# 4G_GATEWAY.net
KiCad netlist of a schematic drawn in Altium Designer
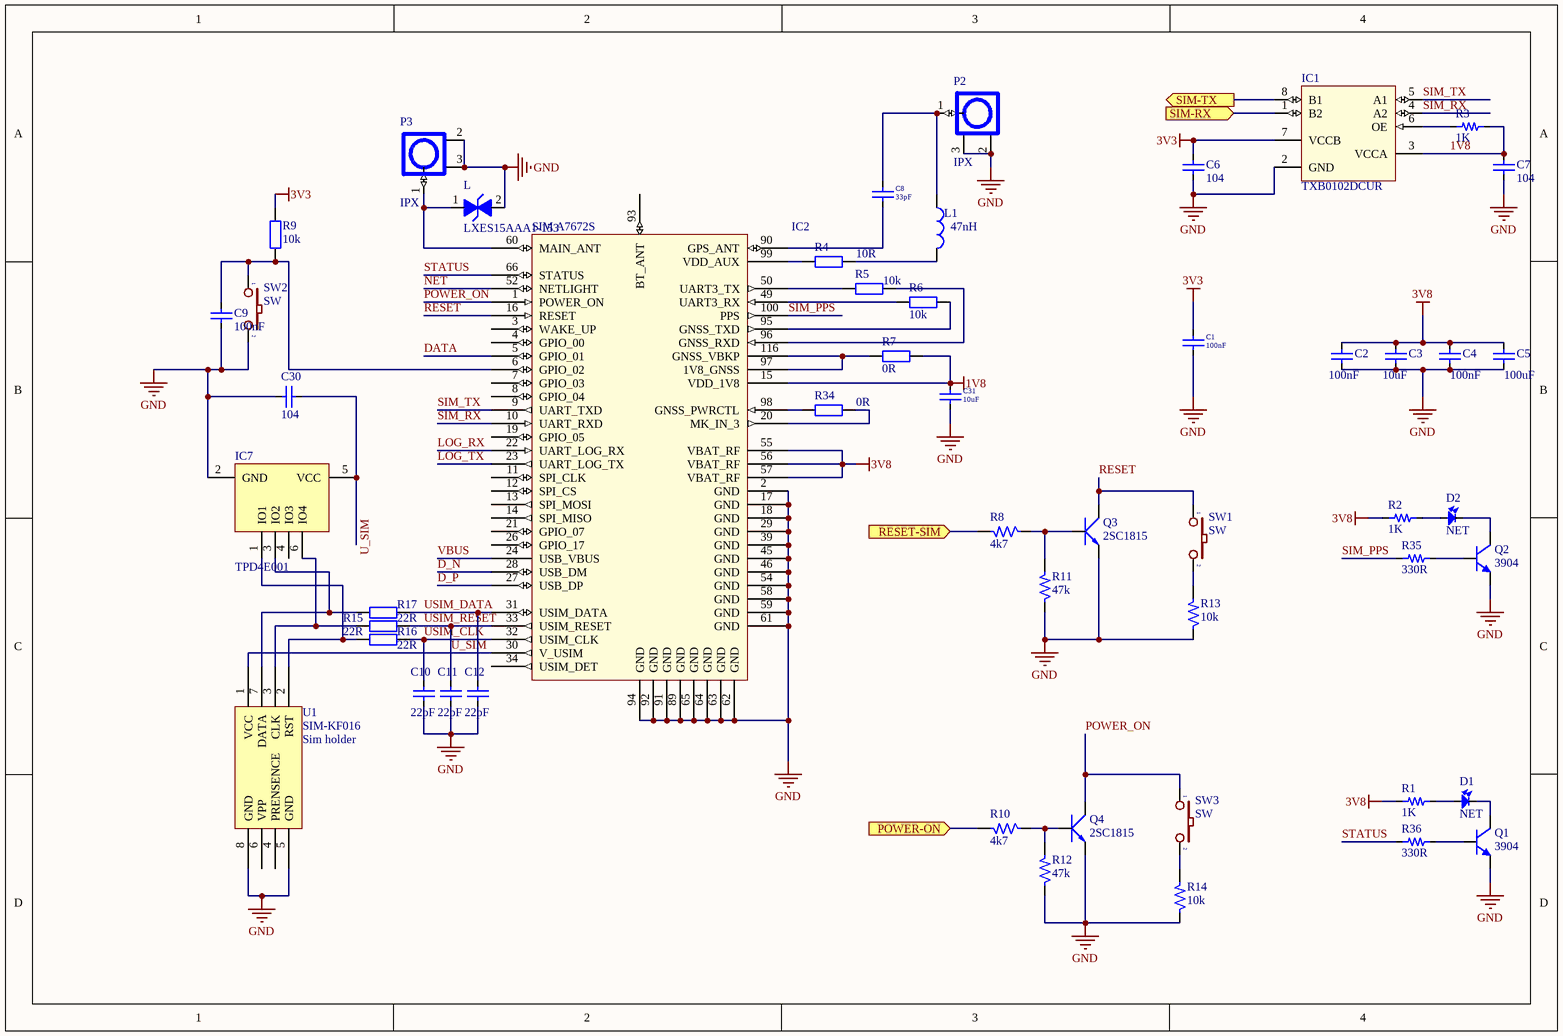
[diagram p0: 4G_GATEWAY.SchDoc]

(export (version "E")
  (design (tool "Eeschema 10.0.6"))
  (components
    (comp (ref "C1")
      (value "100nF")
      (footprint "CAP_0805")
      (description "Capacitor")
      (fields (field (name "PUBLISHER") "Altium Limited"))
      (libsource (lib "SIM_devkit") (part "CapSMD_5"))
    )
    (comp (ref "C2")
      (value "100nF")
      (footprint "CAP_0805")
      (description "Capacitor")
      (fields (field (name "PUBLISHER") "Altium Limited"))
      (libsource (lib "SIM_devkit") (part "CapSMD_9"))
    )
    (comp (ref "C3")
      (value "10uF")
      (footprint "CAP_0805")
      (description "Capacitor")
      (fields (field (name "PUBLISHER") "Altium Limited"))
      (libsource (lib "SIM_devkit") (part "CapSMD_9"))
    )
    (comp (ref "C4")
      (value "100nF")
      (footprint "CAP_0805")
      (description "Capacitor")
      (fields (field (name "PUBLISHER") "Altium Limited"))
      (libsource (lib "SIM_devkit") (part "CapSMD_9"))
    )
    (comp (ref "C5")
      (value "100uF")
      (footprint "CAP_0805")
      (description "Capacitor")
      (fields (field (name "PUBLISHER") "Altium Limited"))
      (libsource (lib "SIM_devkit") (part "CapSMD_9"))
    )
    (comp (ref "C6")
      (value "104")
      (footprint "CAP_0805")
      (description "Capacitor")
      (fields (field (name "PUBLISHER") "Altium Limited"))
      (libsource (lib "SIM_devkit") (part "CapSMD_9"))
    )
    (comp (ref "C7")
      (value "104")
      (footprint "CAP_0805")
      (description "Capacitor")
      (fields (field (name "PUBLISHER") "Altium Limited"))
      (libsource (lib "SIM_devkit") (part "CapSMD_9"))
    )
    (comp (ref "C8")
      (value "33pF")
      (footprint "CAP_0805")
      (description "Capacitor")
      (fields (field (name "PUBLISHER") "Altium Limited"))
      (libsource (lib "SIM_devkit") (part "CapSMD_1"))
    )
    (comp (ref "C9")
      (value "100nF")
      (footprint "CAP_0805")
      (description "Capacitor")
      (fields (field (name "PUBLISHER") "Altium Limited"))
      (libsource (lib "My Library") (part "CapSMD"))
    )
    (comp (ref "C10")
      (value "22pF")
      (footprint "CAP_0805")
      (description "Capacitor")
      (fields (field (name "PUBLISHER") "Altium Limited"))
      (libsource (lib "My Library") (part "CapSMD"))
    )
    (comp (ref "C11")
      (value "22pF")
      (footprint "CAP_0805")
      (description "Capacitor")
      (fields (field (name "PUBLISHER") "Altium Limited"))
      (libsource (lib "My Library") (part "CapSMD"))
    )
    (comp (ref "C12")
      (value "22pF")
      (footprint "CAP_0805")
      (description "Capacitor")
      (fields (field (name "PUBLISHER") "Altium Limited"))
      (libsource (lib "My Library") (part "CapSMD"))
    )
    (comp (ref "C30")
      (value "104")
      (footprint "CAP_0805")
      (description "Capacitor")
      (fields (field (name "PUBLISHER") "Altium Limited"))
      (libsource (lib "My Library") (part "CapSMD"))
    )
    (comp (ref "C31")
      (value "10uF")
      (footprint "CAP_0805")
      (description "Capacitor")
      (fields (field (name "PUBLISHER") "Altium Limited"))
      (libsource (lib "SIM_devkit") (part "CapSMD_1"))
    )
    (comp (ref "D1")
      (value "NET")
      (footprint "LED-0805-Blue")
      (description "LED Single colour Green and Red")
      (libsource (lib "SIM_devkit") (part "LED_2"))
    )
    (comp (ref "D2")
      (value "NET")
      (footprint "LED-0805-Blue")
      (description "LED Single colour Green and Red")
      (libsource (lib "SIM_devkit") (part "LED_2"))
    )
    (comp (ref "IC1")
      (value "TXB0102DCUR")
      (footprint "SOP50P310X90-8N")
      (description "IC TRNSLTR BIDIRECTIONAL US8")
      (fields (field (name "MANUFACTURER") "Texas Instruments"))
      (libsource (lib "SIM_devkit") (part "TXB0102DCUR"))
    )
    (comp (ref "IC2")
      (value "SIM A7672S")
      (footprint "A7672S")
      (description "SIM A7672S-CAT-M1")
      (libsource (lib "My Library") (part "SIM A7672S"))
    )
    (comp (ref "IC7")
      (value "TPD4E001")
      (footprint "SOT23-6")
      (fields (field (name "MANUFACTURER") "Texas Instruments") (field (name "PART NUMBER") "TPD4E001RDBVR"))
      (libsource (lib "SIM_devkit") (part "TPD4E001_1"))
    )
    (comp (ref "L")
      (value "LXES15AAA1-153")
      (footprint "INDC1005X45")
      (description "Clamp Ipp Tvs Diode Surface Mount 1005")
      (fields (field (name "MF") "Murata") (field (name "DIGI-KEY_PART_NUMBER") "490-13210-1-ND"))
      (libsource (lib "LXES15AAA1-153") (part "LXES15AAA1-153"))
    )
    (comp (ref "L1")
      (value "47nH")
      (footprint "L-0805")
      (description "22µH Shielded Inductor 1.65A 96mOhm Max Nonstandard")
      (fields (field (name "MANUFACTURER") "Bourns Inc.") (field (name "PART NUMBER") "SRR0745A-220M"))
      (libsource (lib "SIM_devkit") (part "L1"))
    )
    (comp (ref "P2")
      (value "IPX")
      (footprint "IPXS")
      (description "Antenna GSM GPS")
      (fields
        (field (name "MANUFACTURER") "TE Connectivity AMP Connectors")
        (field (name "PART NUMBER") "2334884-1")
      )
      (libsource (lib "SIM_devkit") (part "IPXSx66"))
    )
    (comp (ref "P3")
      (value "IPX")
      (footprint "IPXS")
      (description "Antenna GSM GPS")
      (fields
        (field (name "MANUFACTURER") "TE Connectivity AMP Connectors")
        (field (name "PART NUMBER") "2334884-1")
      )
      (libsource (lib "SIM_devkit") (part "IPXSx66"))
    )
    (comp (ref "Q1") (value "3904") (footprint "SOT23") (libsource (lib "SIM_devkit") (part "MMBT3904")))
    (comp (ref "Q2") (value "3904") (footprint "SOT23") (libsource (lib "SIM_devkit") (part "MMBT3904")))
    (comp (ref "Q3")
      (value "2SC1815")
      (footprint "SOT23")
      (description "NPN 600mW, ECB")
      (libsource (lib "My Library 2") (part "2SC1815"))
    )
    (comp (ref "Q4")
      (value "2SC1815")
      (footprint "SOT23")
      (description "NPN 600mW, ECB")
      (libsource (lib "My Library 2") (part "2SC1815"))
    )
    (comp (ref "R1")
      (value "1K")
      (footprint "RES-SMD-0805")
      (description "Resistor")
      (fields
        (field (name "MANUFACTURER") "Generic Components")
        (field (name "PUBLISHER") "Altium Hobart Technology Centre")
      )
      (libsource (lib "SIM_devkit") (part "Resistor - SMD"))
    )
    (comp (ref "R2")
      (value "1K")
      (footprint "RES-SMD-0805")
      (description "Resistor")
      (fields
        (field (name "MANUFACTURER") "Generic Components")
        (field (name "PUBLISHER") "Altium Hobart Technology Centre")
      )
      (libsource (lib "SIM_devkit") (part "Resistor - SMD"))
    )
    (comp (ref "R3")
      (value "1K")
      (footprint "RES-SMD-0805")
      (description "Resistor")
      (fields
        (field (name "MANUFACTURER") "Generic Components")
        (field (name "PUBLISHER") "Altium Hobart Technology Centre")
      )
      (libsource (lib "SIM_devkit") (part "Resistor - SMD"))
    )
    (comp (ref "R4")
      (value "10R")
      (footprint "RES-SMD-0805")
      (description "Resistor SMD")
      (fields
        (field (name "MANUFACTURER") "Generic Components")
        (field (name "PUBLISHER") "Altium Hobart Technology Centre")
      )
      (libsource (lib "My Library") (part "Resistor - SMD"))
    )
    (comp (ref "R5")
      (value "10k")
      (footprint "RES-SMD-0805")
      (description "Resistor SMD")
      (fields
        (field (name "MANUFACTURER") "Generic Components")
        (field (name "PUBLISHER") "Altium Hobart Technology Centre")
      )
      (libsource (lib "My Library") (part "Resistor - SMD"))
    )
    (comp (ref "R6")
      (value "10k")
      (footprint "RES-SMD-0805")
      (description "Resistor SMD")
      (fields
        (field (name "MANUFACTURER") "Generic Components")
        (field (name "PUBLISHER") "Altium Hobart Technology Centre")
      )
      (libsource (lib "My Library") (part "Resistor - SMD"))
    )
    (comp (ref "R7")
      (value "0R")
      (footprint "RES-SMD-0805")
      (description "Resistor SMD")
      (fields
        (field (name "MANUFACTURER") "Generic Components")
        (field (name "PUBLISHER") "Altium Hobart Technology Centre")
      )
      (libsource (lib "My Library") (part "Resistor - SMD"))
    )
    (comp (ref "R8")
      (value "4k7")
      (footprint "RES-SMD-0805")
      (description "Resistor 1/4W")
      (libsource (lib "My Library 2") (part "R"))
    )
    (comp (ref "R9")
      (value "10k")
      (footprint "RES-SMD-0805")
      (description "Resistor SMD")
      (fields
        (field (name "MANUFACTURER") "Generic Components")
        (field (name "PUBLISHER") "Altium Hobart Technology Centre")
      )
      (libsource (lib "My Library") (part "Resistor - SMD"))
    )
    (comp (ref "R10")
      (value "4k7")
      (footprint "RES-SMD-0805")
      (description "Resistor 1/4W")
      (libsource (lib "My Library 2") (part "R"))
    )
    (comp (ref "R11")
      (value "47k")
      (footprint "RES-SMD-0805")
      (description "Resistor 1/4W")
      (libsource (lib "My Library 2") (part "R"))
    )
    (comp (ref "R12")
      (value "47k")
      (footprint "RES-SMD-0805")
      (description "Resistor 1/4W")
      (libsource (lib "My Library 2") (part "R"))
    )
    (comp (ref "R13")
      (value "10k")
      (footprint "RES-SMD-0805")
      (description "Resistor 1/4W")
      (libsource (lib "My Library 2") (part "R"))
    )
    (comp (ref "R14")
      (value "10k")
      (footprint "RES-SMD-0805")
      (description "Resistor 1/4W")
      (libsource (lib "My Library 2") (part "R"))
    )
    (comp (ref "R15")
      (value "22R")
      (footprint "RES-SMD-0805")
      (description "Resistor SMD")
      (fields
        (field (name "MANUFACTURER") "Generic Components")
        (field (name "PUBLISHER") "Altium Hobart Technology Centre")
      )
      (libsource (lib "My Library") (part "Resistor - SMD"))
    )
    (comp (ref "R16")
      (value "22R")
      (footprint "RES-SMD-0805")
      (description "Resistor SMD")
      (fields
        (field (name "MANUFACTURER") "Generic Components")
        (field (name "PUBLISHER") "Altium Hobart Technology Centre")
      )
      (libsource (lib "My Library") (part "Resistor - SMD"))
    )
    (comp (ref "R17")
      (value "22R")
      (footprint "RES-SMD-0805")
      (description "Resistor SMD")
      (fields
        (field (name "MANUFACTURER") "Generic Components")
        (field (name "PUBLISHER") "Altium Hobart Technology Centre")
      )
      (libsource (lib "My Library") (part "Resistor - SMD"))
    )
    (comp (ref "R34")
      (value "0R")
      (footprint "RES-SMD-0805")
      (description "Resistor SMD")
      (fields
        (field (name "MANUFACTURER") "Generic Components")
        (field (name "PUBLISHER") "Altium Hobart Technology Centre")
      )
      (libsource (lib "My Library") (part "Resistor - SMD"))
    )
    (comp (ref "R35")
      (value "330R")
      (footprint "RES-SMD-0805")
      (description "Resistor")
      (fields
        (field (name "MANUFACTURER") "Generic Components")
        (field (name "PUBLISHER") "Altium Hobart Technology Centre")
      )
      (libsource (lib "SIM_devkit") (part "Resistor - SMD"))
    )
    (comp (ref "R36")
      (value "330R")
      (footprint "RES-SMD-0805")
      (description "Resistor")
      (fields
        (field (name "MANUFACTURER") "Generic Components")
        (field (name "PUBLISHER") "Altium Hobart Technology Centre")
      )
      (libsource (lib "SIM_devkit") (part "Resistor - SMD"))
    )
    (comp (ref "SW1")
      (value "SW")
      (footprint "SW-SMD")
      (description "Switch button 2 pin")
      (libsource (lib "My Library 2") (part "SW2"))
    )
    (comp (ref "SW2")
      (value "SW")
      (footprint "SW-SMD")
      (description "Switch button 2 pin")
      (libsource (lib "My Library") (part "SW2"))
    )
    (comp (ref "SW3")
      (value "SW")
      (footprint "SW-SMD")
      (description "Switch button 2 pin")
      (libsource (lib "My Library 2") (part "SW2"))
    )
    (comp (ref "U1")
      (value "SIM-KF016")
      (footprint "SIM_MicroSIM 6P Flip")
      (description "SIM Card Holder KF-016")
      (fields (field (name "ALTIUM_VALUE") "Sim holder"))
      (libsource (lib "My Library") (part "Sim holder"))
    )
  )
  (nets
    (net (code "1") (name "/DATA") (class "Default")
      (node (ref "IC2") (pin "5") (pinfunction "GPIO_01_5") (pintype "bidirectional"))
    )
    (net (code "2") (name "/D_N") (class "Default")
      (node (ref "IC2") (pin "28") (pinfunction "USB_DM_28") (pintype "bidirectional"))
    )
    (net (code "3") (name "/D_P") (class "Default")
      (node (ref "IC2") (pin "27") (pinfunction "USB_DP_27") (pintype "bidirectional"))
    )
    (net (code "4") (name "/LOG_RX") (class "Default")
      (node (ref "IC2") (pin "22") (pinfunction "UART_LOG_RX_22") (pintype "input"))
    )
    (net (code "5") (name "/LOG_TX") (class "Default")
      (node (ref "IC2") (pin "23") (pinfunction "UART_LOG_TX_23") (pintype "output"))
    )
    (net (code "6") (name "/NET") (class "Default")
      (node (ref "IC2") (pin "52") (pinfunction "NETLIGHT_52") (pintype "bidirectional"))
    )
    (net (code "7") (name "/POWER-ON") (class "Default")
      (node (ref "R10") (pin "2") (pinfunction "2_2") (pintype "passive"))
    )
    (net (code "8") (name "/POWER_ON") (class "Default")
      (node (ref "IC2") (pin "1") (pinfunction "POWER_ON_1") (pintype "input"))
      (node (ref "Q4") (pin "2") (pinfunction "C_2") (pintype "passive"))
      (node (ref "SW3") (pin "1") (pinfunction "1_1") (pintype "passive"))
    )
    (net (code "9") (name "/RESET") (class "Default")
      (node (ref "IC2") (pin "16") (pinfunction "RESET_16") (pintype "input"))
      (node (ref "Q3") (pin "2") (pinfunction "C_2") (pintype "passive"))
      (node (ref "SW1") (pin "1") (pinfunction "1_1") (pintype "passive"))
    )
    (net (code "10") (name "/RESET-SIM") (class "Default")
      (node (ref "R8") (pin "2") (pinfunction "2_2") (pintype "passive"))
    )
    (net (code "11") (name "/SIM-RX") (class "Default")
      (node (ref "IC1") (pin "1") (pinfunction "B2_1") (pintype "bidirectional"))
    )
    (net (code "12") (name "/SIM-TX") (class "Default")
      (node (ref "IC1") (pin "8") (pinfunction "B1_8") (pintype "bidirectional"))
    )
    (net (code "13") (name "/SIM_PPS") (class "Default")
      (node (ref "IC2") (pin "100") (pinfunction "PPS_100") (pintype "output"))
      (node (ref "R35") (pin "1") (pinfunction "1_1") (pintype "passive"))
    )
    (net (code "14") (name "/SIM_RX") (class "Default")
      (node (ref "IC1") (pin "4") (pinfunction "A2_4") (pintype "bidirectional"))
      (node (ref "IC2") (pin "10") (pinfunction "UART_RXD_10") (pintype "input"))
    )
    (net (code "15") (name "/SIM_TX") (class "Default")
      (node (ref "IC1") (pin "5") (pinfunction "A1_5") (pintype "bidirectional"))
      (node (ref "IC2") (pin "9") (pinfunction "UART_TXD_9") (pintype "output"))
    )
    (net (code "16") (name "/STATUS") (class "Default")
      (node (ref "IC2") (pin "66") (pinfunction "STATUS_66") (pintype "bidirectional"))
      (node (ref "R36") (pin "1") (pinfunction "1_1") (pintype "passive"))
    )
    (net (code "17") (name "/USIM_CLK") (class "Default")
      (node (ref "C10") (pin "1") (pinfunction "1_1") (pintype "passive"))
      (node (ref "IC2") (pin "32") (pinfunction "USIM_CLK_32") (pintype "output"))
      (node (ref "R16") (pin "1") (pinfunction "1_1") (pintype "passive"))
    )
    (net (code "18") (name "/USIM_DATA") (class "Default")
      (node (ref "C12") (pin "1") (pinfunction "1_1") (pintype "passive"))
      (node (ref "IC2") (pin "31") (pinfunction "USIM_DATA_31") (pintype "bidirectional"))
      (node (ref "R17") (pin "1") (pinfunction "1_1") (pintype "passive"))
    )
    (net (code "19") (name "/USIM_RESET") (class "Default")
      (node (ref "C11") (pin "1") (pinfunction "1_1") (pintype "passive"))
      (node (ref "C30") (pin "1") (pinfunction "1_1") (pintype "passive"))
      (node (ref "IC2") (pin "30") (pinfunction "V_USIM_30") (pintype "output"))
      (node (ref "IC2") (pin "33") (pinfunction "USIM_RESET_33") (pintype "output"))
      (node (ref "IC7") (pin "5") (pinfunction "VCC_5") (pintype "passive"))
      (node (ref "R15") (pin "2") (pinfunction "2_2") (pintype "passive"))
      (node (ref "U1") (pin "1") (pinfunction "VCC_1") (pintype "passive"))
    )
    (net (code "20") (name "/VBUS") (class "Default")
      (node (ref "IC2") (pin "24") (pinfunction "USB_VBUS_24") (pintype "passive"))
    )
    (net (code "21") (name "1V8") (class "Default")
      (node (ref "C31") (pin "2") (pinfunction "2_2") (pintype "passive"))
      (node (ref "C7") (pin "2") (pinfunction "2_2") (pintype "passive"))
      (node (ref "IC1") (pin "3") (pinfunction "VCCA_3") (pintype "power_in"))
      (node (ref "IC2") (pin "15") (pinfunction "VDD_1V8_15") (pintype "passive"))
      (node (ref "R3") (pin "2") (pinfunction "2_2") (pintype "passive"))
      (node (ref "R7") (pin "1") (pinfunction "1_1") (pintype "passive"))
    )
    (net (code "22") (name "3V3") (class "Default")
      (node (ref "C1") (pin "2") (pinfunction "2_2") (pintype "passive"))
      (node (ref "C6") (pin "2") (pinfunction "2_2") (pintype "passive"))
      (node (ref "IC1") (pin "7") (pinfunction "VCCB_7") (pintype "power_in"))
      (node (ref "R9") (pin "2") (pinfunction "2_2") (pintype "passive"))
    )
    (net (code "23") (name "3V8") (class "Default")
      (node (ref "C2") (pin "2") (pinfunction "2_2") (pintype "passive"))
      (node (ref "C3") (pin "2") (pinfunction "2_2") (pintype "passive"))
      (node (ref "C4") (pin "2") (pinfunction "2_2") (pintype "passive"))
      (node (ref "C5") (pin "2") (pinfunction "2_2") (pintype "passive"))
      (node (ref "IC2") (pin "55") (pinfunction "VBAT_RF_55") (pintype "passive"))
      (node (ref "IC2") (pin "56") (pinfunction "VBAT_RF_56") (pintype "passive"))
      (node (ref "IC2") (pin "57") (pinfunction "VBAT_RF_57") (pintype "passive"))
      (node (ref "R1") (pin "1") (pinfunction "1_1") (pintype "passive"))
      (node (ref "R2") (pin "1") (pinfunction "1_1") (pintype "passive"))
    )
    (net (code "24") (name "GND") (class "Default")
      (node (ref "C1") (pin "1") (pinfunction "1_1") (pintype "passive"))
      (node (ref "C10") (pin "2") (pinfunction "2_2") (pintype "passive"))
      (node (ref "C11") (pin "2") (pinfunction "2_2") (pintype "passive"))
      (node (ref "C12") (pin "2") (pinfunction "2_2") (pintype "passive"))
      (node (ref "C2") (pin "1") (pinfunction "1_1") (pintype "passive"))
      (node (ref "C3") (pin "1") (pinfunction "1_1") (pintype "passive"))
      (node (ref "C30") (pin "2") (pinfunction "2_2") (pintype "passive"))
      (node (ref "C31") (pin "1") (pinfunction "1_1") (pintype "passive"))
      (node (ref "C4") (pin "1") (pinfunction "1_1") (pintype "passive"))
      (node (ref "C5") (pin "1") (pinfunction "1_1") (pintype "passive"))
      (node (ref "C6") (pin "1") (pinfunction "1_1") (pintype "passive"))
      (node (ref "C7") (pin "1") (pinfunction "1_1") (pintype "passive"))
      (node (ref "C9") (pin "1") (pinfunction "1_1") (pintype "passive"))
      (node (ref "IC1") (pin "2") (pinfunction "GND_2") (pintype "power_in"))
      (node (ref "IC2") (pin "17") (pinfunction "GND_17") (pintype "passive"))
      (node (ref "IC2") (pin "18") (pinfunction "GND_18") (pintype "passive"))
      (node (ref "IC2") (pin "2") (pinfunction "GND_2") (pintype "passive"))
      (node (ref "IC2") (pin "29") (pinfunction "GND_29") (pintype "passive"))
      (node (ref "IC2") (pin "39") (pinfunction "GND_39") (pintype "passive"))
      (node (ref "IC2") (pin "45") (pinfunction "GND_45") (pintype "passive"))
      (node (ref "IC2") (pin "46") (pinfunction "GND_46") (pintype "passive"))
      (node (ref "IC2") (pin "54") (pinfunction "GND_54") (pintype "passive"))
      (node (ref "IC2") (pin "58") (pinfunction "GND_58") (pintype "passive"))
      (node (ref "IC2") (pin "59") (pinfunction "GND_59") (pintype "passive"))
      (node (ref "IC2") (pin "61") (pinfunction "GND_61") (pintype "passive"))
      (node (ref "IC2") (pin "62") (pinfunction "GND_62") (pintype "passive"))
      (node (ref "IC2") (pin "63") (pinfunction "GND_63") (pintype "passive"))
      (node (ref "IC2") (pin "64") (pinfunction "GND_64") (pintype "passive"))
      (node (ref "IC2") (pin "65") (pinfunction "GND_65") (pintype "passive"))
      (node (ref "IC2") (pin "89") (pinfunction "GND_89") (pintype "passive"))
      (node (ref "IC2") (pin "91") (pinfunction "GND_91") (pintype "passive"))
      (node (ref "IC2") (pin "92") (pinfunction "GND_92") (pintype "passive"))
      (node (ref "IC2") (pin "94") (pinfunction "GND_94") (pintype "passive"))
      (node (ref "IC7") (pin "2") (pinfunction "GND_2") (pintype "passive"))
      (node (ref "L") (pin "2") (pinfunction "2_2") (pintype "passive"))
      (node (ref "P2") (pin "2") (pintype "passive"))
      (node (ref "P2") (pin "3") (pintype "passive"))
      (node (ref "P3") (pin "2") (pintype "passive"))
      (node (ref "P3") (pin "3") (pintype "passive"))
      (node (ref "Q1") (pin "2") (pinfunction "E_2") (pintype "passive"))
      (node (ref "Q2") (pin "2") (pinfunction "E_2") (pintype "passive"))
      (node (ref "Q3") (pin "1") (pinfunction "E_1") (pintype "passive"))
      (node (ref "Q4") (pin "1") (pinfunction "E_1") (pintype "passive"))
      (node (ref "R11") (pin "1") (pinfunction "1_1") (pintype "passive"))
      (node (ref "R12") (pin "1") (pinfunction "1_1") (pintype "passive"))
      (node (ref "R13") (pin "1") (pinfunction "1_1") (pintype "passive"))
      (node (ref "R14") (pin "1") (pinfunction "1_1") (pintype "passive"))
      (node (ref "SW2") (pin "2") (pinfunction "2_2") (pintype "passive"))
      (node (ref "U1") (pin "5") (pinfunction "GND_5") (pintype "passive"))
      (node (ref "U1") (pin "8") (pinfunction "GND_8") (pintype "passive"))
    )
    (net (code "25") (name "Net-(C8-Pad2)") (class "Default")
      (node (ref "C8") (pin "2") (pinfunction "2_2") (pintype "passive"))
      (node (ref "L1") (pin "1") (pinfunction "1_1") (pintype "passive"))
      (node (ref "P2") (pin "1") (pintype "bidirectional"))
    )
    (net (code "26") (name "Net-(D1-Pad1)") (class "Default")
      (node (ref "D1") (pin "1") (pinfunction "1_1") (pintype "passive"))
      (node (ref "R1") (pin "2") (pinfunction "2_2") (pintype "passive"))
    )
    (net (code "27") (name "Net-(D2-Pad1)") (class "Default")
      (node (ref "D2") (pin "1") (pinfunction "1_1") (pintype "passive"))
      (node (ref "R2") (pin "2") (pinfunction "2_2") (pintype "passive"))
    )
    (net (code "28") (name "Net-(IC1-OE)") (class "Default")
      (node (ref "IC1") (pin "6") (pinfunction "OE_6") (pintype "input"))
      (node (ref "R3") (pin "1") (pinfunction "1_1") (pintype "passive"))
    )
    (net (code "29") (name "Net-(IC2-1V8_GNSS)") (class "Default")
      (node (ref "IC2") (pin "116") (pinfunction "GNSS_VBKP_116") (pintype "passive"))
      (node (ref "IC2") (pin "97") (pinfunction "1V8_GNSS_97") (pintype "passive"))
      (node (ref "R7") (pin "2") (pinfunction "2_2") (pintype "passive"))
    )
    (net (code "30") (name "Net-(IC2-GNSS_PWRCTL)") (class "Default")
      (node (ref "IC2") (pin "98") (pinfunction "GNSS_PWRCTL_98") (pintype "input"))
      (node (ref "R34") (pin "2") (pinfunction "2_2") (pintype "passive"))
    )
    (net (code "31") (name "Net-(IC2-GNSS_RXD)") (class "Default")
      (node (ref "IC2") (pin "96") (pinfunction "GNSS_RXD_96") (pintype "input"))
      (node (ref "R5") (pin "1") (pinfunction "1_1") (pintype "passive"))
    )
    (net (code "32") (name "Net-(IC2-GNSS_TXD)") (class "Default")
      (node (ref "IC2") (pin "95") (pinfunction "GNSS_TXD_95") (pintype "output"))
      (node (ref "R6") (pin "1") (pinfunction "1_1") (pintype "passive"))
    )
    (net (code "33") (name "Net-(IC2-GPIO_02)") (class "Default")
      (node (ref "C9") (pin "2") (pinfunction "2_2") (pintype "passive"))
      (node (ref "IC2") (pin "6") (pinfunction "GPIO_02_6") (pintype "bidirectional"))
      (node (ref "R9") (pin "1") (pinfunction "1_1") (pintype "passive"))
      (node (ref "SW2") (pin "1") (pinfunction "1_1") (pintype "passive"))
    )
    (net (code "34") (name "Net-(IC2-GPS_ANT)") (class "Default")
      (node (ref "C8") (pin "1") (pinfunction "1_1") (pintype "passive"))
      (node (ref "IC2") (pin "90") (pinfunction "GPS_ANT_90") (pintype "bidirectional"))
    )
    (net (code "35") (name "Net-(IC2-MAIN_ANT)") (class "Default")
      (node (ref "IC2") (pin "60") (pinfunction "MAIN_ANT_60") (pintype "bidirectional"))
      (node (ref "L") (pin "1") (pinfunction "1_1") (pintype "passive"))
      (node (ref "P3") (pin "1") (pintype "bidirectional"))
    )
    (net (code "36") (name "Net-(IC2-MK_IN_3)") (class "Default")
      (node (ref "IC2") (pin "20") (pinfunction "MK_IN_3_20") (pintype "output"))
      (node (ref "R34") (pin "1") (pinfunction "1_1") (pintype "passive"))
    )
    (net (code "37") (name "Net-(IC2-UART3_RX)") (class "Default")
      (node (ref "IC2") (pin "49") (pinfunction "UART3_RX_49") (pintype "input"))
      (node (ref "R6") (pin "2") (pinfunction "2_2") (pintype "passive"))
    )
    (net (code "38") (name "Net-(IC2-UART3_TX)") (class "Default")
      (node (ref "IC2") (pin "50") (pinfunction "UART3_TX_50") (pintype "output"))
      (node (ref "R5") (pin "2") (pinfunction "2_2") (pintype "passive"))
    )
    (net (code "39") (name "Net-(IC2-VDD_AUX)") (class "Default")
      (node (ref "IC2") (pin "99") (pinfunction "VDD_AUX_99") (pintype "passive"))
      (node (ref "R4") (pin "2") (pinfunction "2_2") (pintype "passive"))
    )
    (net (code "40") (name "Net-(IC7-IO1)") (class "Default")
      (node (ref "IC7") (pin "1") (pinfunction "IO1_1") (pintype "passive"))
      (node (ref "R16") (pin "2") (pinfunction "2_2") (pintype "passive"))
      (node (ref "U1") (pin "2") (pinfunction "RST_2") (pintype "passive"))
    )
    (net (code "41") (name "Net-(IC7-IO2)") (class "Default")
      (node (ref "IC7") (pin "3") (pinfunction "IO2_3") (pintype "passive"))
      (node (ref "R17") (pin "2") (pinfunction "2_2") (pintype "passive"))
      (node (ref "U1") (pin "7") (pinfunction "DATA_7") (pintype "passive"))
    )
    (net (code "42") (name "Net-(IC7-IO4)") (class "Default")
      (node (ref "IC7") (pin "6") (pinfunction "IO4_6") (pintype "passive"))
      (node (ref "R15") (pin "1") (pinfunction "1_1") (pintype "passive"))
      (node (ref "U1") (pin "3") (pinfunction "CLK_3") (pintype "passive"))
    )
    (net (code "43") (name "Net-(L1-Pad2)") (class "Default")
      (node (ref "L1") (pin "2") (pinfunction "2_2") (pintype "passive"))
      (node (ref "R4") (pin "1") (pinfunction "1_1") (pintype "passive"))
    )
    (net (code "44") (name "Net-(Q1-B)") (class "Default")
      (node (ref "Q1") (pin "1") (pinfunction "B_1") (pintype "passive"))
      (node (ref "R36") (pin "2") (pinfunction "2_2") (pintype "passive"))
    )
    (net (code "45") (name "Net-(Q1-C)") (class "Default")
      (node (ref "D1") (pin "2") (pinfunction "2_2") (pintype "passive"))
      (node (ref "Q1") (pin "3") (pinfunction "C_3") (pintype "passive"))
    )
    (net (code "46") (name "Net-(Q2-B)") (class "Default")
      (node (ref "Q2") (pin "1") (pinfunction "B_1") (pintype "passive"))
      (node (ref "R35") (pin "2") (pinfunction "2_2") (pintype "passive"))
    )
    (net (code "47") (name "Net-(Q2-C)") (class "Default")
      (node (ref "D2") (pin "2") (pinfunction "2_2") (pintype "passive"))
      (node (ref "Q2") (pin "3") (pinfunction "C_3") (pintype "passive"))
    )
    (net (code "48") (name "Net-(Q3-B)") (class "Default")
      (node (ref "Q3") (pin "3") (pinfunction "B_3") (pintype "passive"))
      (node (ref "R11") (pin "2") (pinfunction "2_2") (pintype "passive"))
      (node (ref "R8") (pin "1") (pinfunction "1_1") (pintype "passive"))
    )
    (net (code "49") (name "Net-(Q4-B)") (class "Default")
      (node (ref "Q4") (pin "3") (pinfunction "B_3") (pintype "passive"))
      (node (ref "R10") (pin "1") (pinfunction "1_1") (pintype "passive"))
      (node (ref "R12") (pin "2") (pinfunction "2_2") (pintype "passive"))
    )
    (net (code "50") (name "Net-(R13-Pad2)") (class "Default")
      (node (ref "R13") (pin "2") (pinfunction "2_2") (pintype "passive"))
      (node (ref "SW1") (pin "2") (pinfunction "2_2") (pintype "passive"))
    )
    (net (code "51") (name "Net-(R14-Pad2)") (class "Default")
      (node (ref "R14") (pin "2") (pinfunction "2_2") (pintype "passive"))
      (node (ref "SW3") (pin "2") (pinfunction "2_2") (pintype "passive"))
    )
    (net (code "52") (name "unconnected-(IC2-ADC1-Pad47)") (class "Default")
      (node (ref "IC2") (pin "47") (pinfunction "ADC1_47") (pintype "passive"))
    )
    (net (code "53") (name "unconnected-(IC2-ADC2-Pad46)") (class "Default")
      (node (ref "IC2") (pin "46") (pinfunction "ADC2_46") (pintype "passive"))
    )
    (net (code "54") (name "unconnected-(IC2-BT_ANT-Pad93)") (class "Default")
      (node (ref "IC2") (pin "93") (pinfunction "BT_ANT_93") (pintype "bidirectional"))
    )
    (net (code "55") (name "unconnected-(IC2-EAR1N-Pad25)") (class "Default")
      (node (ref "IC2") (pin "25") (pinfunction "EAR1N_25") (pintype "passive"))
    )
    (net (code "56") (name "unconnected-(IC2-EAR1P-Pad26)") (class "Default")
      (node (ref "IC2") (pin "26") (pinfunction "EAR1P_26") (pintype "passive"))
    )
    (net (code "57") (name "unconnected-(IC2-GPIO1-Pad51)") (class "Default")
      (node (ref "IC2") (pin "51") (pinfunction "GPIO1_51") (pintype "passive"))
    )
    (net (code "58") (name "unconnected-(IC2-GPIO4-Pad54)") (class "Default")
      (node (ref "IC2") (pin "54") (pinfunction "GPIO4_54") (pintype "passive"))
    )
    (net (code "59") (name "unconnected-(IC2-GPIO40-Pad49)") (class "Default")
      (node (ref "IC2") (pin "49") (pinfunction "GPIO40_49") (pintype "passive"))
    )
    (net (code "60") (name "unconnected-(IC2-GPIO41-Pad52)") (class "Default")
      (node (ref "IC2") (pin "52") (pinfunction "GPIO41_52") (pintype "passive"))
    )
    (net (code "61") (name "unconnected-(IC2-GPIO42-Pad53)") (class "Default")
      (node (ref "IC2") (pin "53") (pinfunction "GPIO42_53") (pintype "passive"))
    )
    (net (code "62") (name "unconnected-(IC2-GPIO43-Pad50)") (class "Default")
      (node (ref "IC2") (pin "50") (pinfunction "GPIO43_50") (pintype "passive"))
    )
    (net (code "63") (name "unconnected-(IC2-GPIO44-Pad48)") (class "Default")
      (node (ref "IC2") (pin "48") (pinfunction "GPIO44_48") (pintype "passive"))
    )
    (net (code "64") (name "unconnected-(IC2-GPIO_00-Pad4)") (class "Default")
      (node (ref "IC2") (pin "4") (pinfunction "GPIO_00_4") (pintype "bidirectional"))
    )
    (net (code "65") (name "unconnected-(IC2-GPIO_03-Pad7)") (class "Default")
      (node (ref "IC2") (pin "7") (pinfunction "GPIO_03_7") (pintype "bidirectional"))
    )
    (net (code "66") (name "unconnected-(IC2-GPIO_04-Pad8)") (class "Default")
      (node (ref "IC2") (pin "8") (pinfunction "GPIO_04_8") (pintype "bidirectional"))
    )
    (net (code "67") (name "unconnected-(IC2-GPIO_05-Pad19)") (class "Default")
      (node (ref "IC2") (pin "19") (pinfunction "GPIO_05_19") (pintype "bidirectional"))
    )
    (net (code "68") (name "unconnected-(IC2-GPIO_07-Pad21)") (class "Default")
      (node (ref "IC2") (pin "21") (pinfunction "GPIO_07_21") (pintype "bidirectional"))
    )
    (net (code "69") (name "unconnected-(IC2-GPIO_17-Pad26)") (class "Default")
      (node (ref "IC2") (pin "26") (pinfunction "GPIO_17_26") (pintype "bidirectional"))
    )
    (net (code "70") (name "unconnected-(IC2-KEYPAD_0-Pad29)") (class "Default")
      (node (ref "IC2") (pin "29") (pinfunction "KEYPAD_0_29") (pintype "passive"))
    )
    (net (code "71") (name "unconnected-(IC2-KEYPAD_1-Pad33)") (class "Default")
      (node (ref "IC2") (pin "33") (pinfunction "KEYPAD_1_33") (pintype "passive"))
    )
    (net (code "72") (name "unconnected-(IC2-KEYPAD_2-Pad30)") (class "Default")
      (node (ref "IC2") (pin "30") (pinfunction "KEYPAD_2_30") (pintype "passive"))
    )
    (net (code "73") (name "unconnected-(IC2-KEYPAD_3-Pad35)") (class "Default")
      (node (ref "IC2") (pin "35") (pinfunction "KEYPAD_3_35") (pintype "passive"))
    )
    (net (code "74") (name "unconnected-(IC2-KEYPAD_4-Pad34)") (class "Default")
      (node (ref "IC2") (pin "34") (pinfunction "KEYPAD_4_34") (pintype "passive"))
    )
    (net (code "75") (name "unconnected-(IC2-KEYSENSE_N0-Pad28)") (class "Default")
      (node (ref "IC2") (pin "28") (pinfunction "KEYSENSE_N0_28") (pintype "passive"))
    )
    (net (code "76") (name "unconnected-(IC2-KEYSENSE_N1-Pad27)") (class "Default")
      (node (ref "IC2") (pin "27") (pinfunction "KEYSENSE_N1_27") (pintype "passive"))
    )
    (net (code "77") (name "unconnected-(IC2-KEYSENSE_N2-Pad31)") (class "Default")
      (node (ref "IC2") (pin "31") (pinfunction "KEYSENSE_N2_31") (pintype "passive"))
    )
    (net (code "78") (name "unconnected-(IC2-KEYSENSE_N3-Pad32)") (class "Default")
      (node (ref "IC2") (pin "32") (pinfunction "KEYSENSE_N3_32") (pintype "passive"))
    )
    (net (code "79") (name "unconnected-(IC2-KEYSENSE_N4-Pad36)") (class "Default")
      (node (ref "IC2") (pin "36") (pinfunction "KEYSENSE_N4_36") (pintype "passive"))
    )
    (net (code "80") (name "unconnected-(IC2-MIC1N-Pad24)") (class "Default")
      (node (ref "IC2") (pin "24") (pinfunction "MIC1N_24") (pintype "passive"))
    )
    (net (code "81") (name "unconnected-(IC2-MIC1P-Pad23)") (class "Default")
      (node (ref "IC2") (pin "23") (pinfunction "MIC1P_23") (pintype "passive"))
    )
    (net (code "82") (name "unconnected-(IC2-PCM_CLK-Pad76)") (class "Default")
      (node (ref "IC2") (pin "76") (pinfunction "PCM_CLK_76") (pintype "passive"))
    )
    (net (code "83") (name "unconnected-(IC2-PCM_DIN-Pad74)") (class "Default")
      (node (ref "IC2") (pin "74") (pinfunction "PCM_DIN_74") (pintype "passive"))
    )
    (net (code "84") (name "unconnected-(IC2-PCM_DOUT-Pad73)") (class "Default")
      (node (ref "IC2") (pin "73") (pinfunction "PCM_DOUT_73") (pintype "passive"))
    )
    (net (code "85") (name "unconnected-(IC2-PCM_SYNC-Pad75)") (class "Default")
      (node (ref "IC2") (pin "75") (pinfunction "PCM_SYNC_75") (pintype "passive"))
    )
    (net (code "86") (name "unconnected-(IC2-RESERVED-Pad15)") (class "Default")
      (node (ref "IC2") (pin "15") (pinfunction "RESERVED_15") (pintype "passive"))
    )
    (net (code "87") (name "unconnected-(IC2-RESERVED-Pad16)") (class "Default")
      (node (ref "IC2") (pin "16") (pinfunction "RESERVED_16") (pintype "passive"))
    )
    (net (code "88") (name "unconnected-(IC2-SPI_CLK-Pad11)") (class "Default")
      (node (ref "IC2") (pin "11") (pinfunction "SPI_CLK_11") (pintype "bidirectional"))
    )
    (net (code "89") (name "unconnected-(IC2-SPI_CS-Pad12)") (class "Default")
      (node (ref "IC2") (pin "12") (pinfunction "SPI_CS_12") (pintype "bidirectional"))
    )
    (net (code "90") (name "unconnected-(IC2-SPI_MISO-Pad14)") (class "Default")
      (node (ref "IC2") (pin "14") (pinfunction "SPI_MISO_14") (pintype "output"))
    )
    (net (code "91") (name "unconnected-(IC2-SPI_MOSI-Pad13)") (class "Default")
      (node (ref "IC2") (pin "13") (pinfunction "SPI_MOSI_13") (pintype "output"))
    )
    (net (code "92") (name "unconnected-(IC2-SPK_M-Pad21)") (class "Default")
      (node (ref "IC2") (pin "21") (pinfunction "SPK_M_21") (pintype "passive"))
    )
    (net (code "93") (name "unconnected-(IC2-SPK_P-Pad22)") (class "Default")
      (node (ref "IC2") (pin "22") (pinfunction "SPK_P_22") (pintype "passive"))
    )
    (net (code "94") (name "unconnected-(IC2-USIM_DET-Pad34)") (class "Default")
      (node (ref "IC2") (pin "34") (pinfunction "USIM_DET_34") (pintype "output"))
    )
    (net (code "95") (name "unconnected-(IC2-WAKE_UP-Pad3)") (class "Default")
      (node (ref "IC2") (pin "3") (pinfunction "WAKE_UP_3") (pintype "bidirectional"))
    )
    (net (code "96") (name "unconnected-(IC7-IO3-Pad4)") (class "Default")
      (node (ref "IC7") (pin "4") (pinfunction "IO3_4") (pintype "passive"))
    )
    (net (code "97") (name "unconnected-(U1-PRENSENCE-Pad4)") (class "Default")
      (node (ref "U1") (pin "4") (pinfunction "PRENSENCE_4") (pintype "passive"))
    )
    (net (code "98") (name "unconnected-(U1-VPP-Pad6)") (class "Default")
      (node (ref "U1") (pin "6") (pinfunction "VPP_6") (pintype "passive"))
    )
  )
)
